# LED.net
KiCad netlist of a schematic drawn in Altium Designer
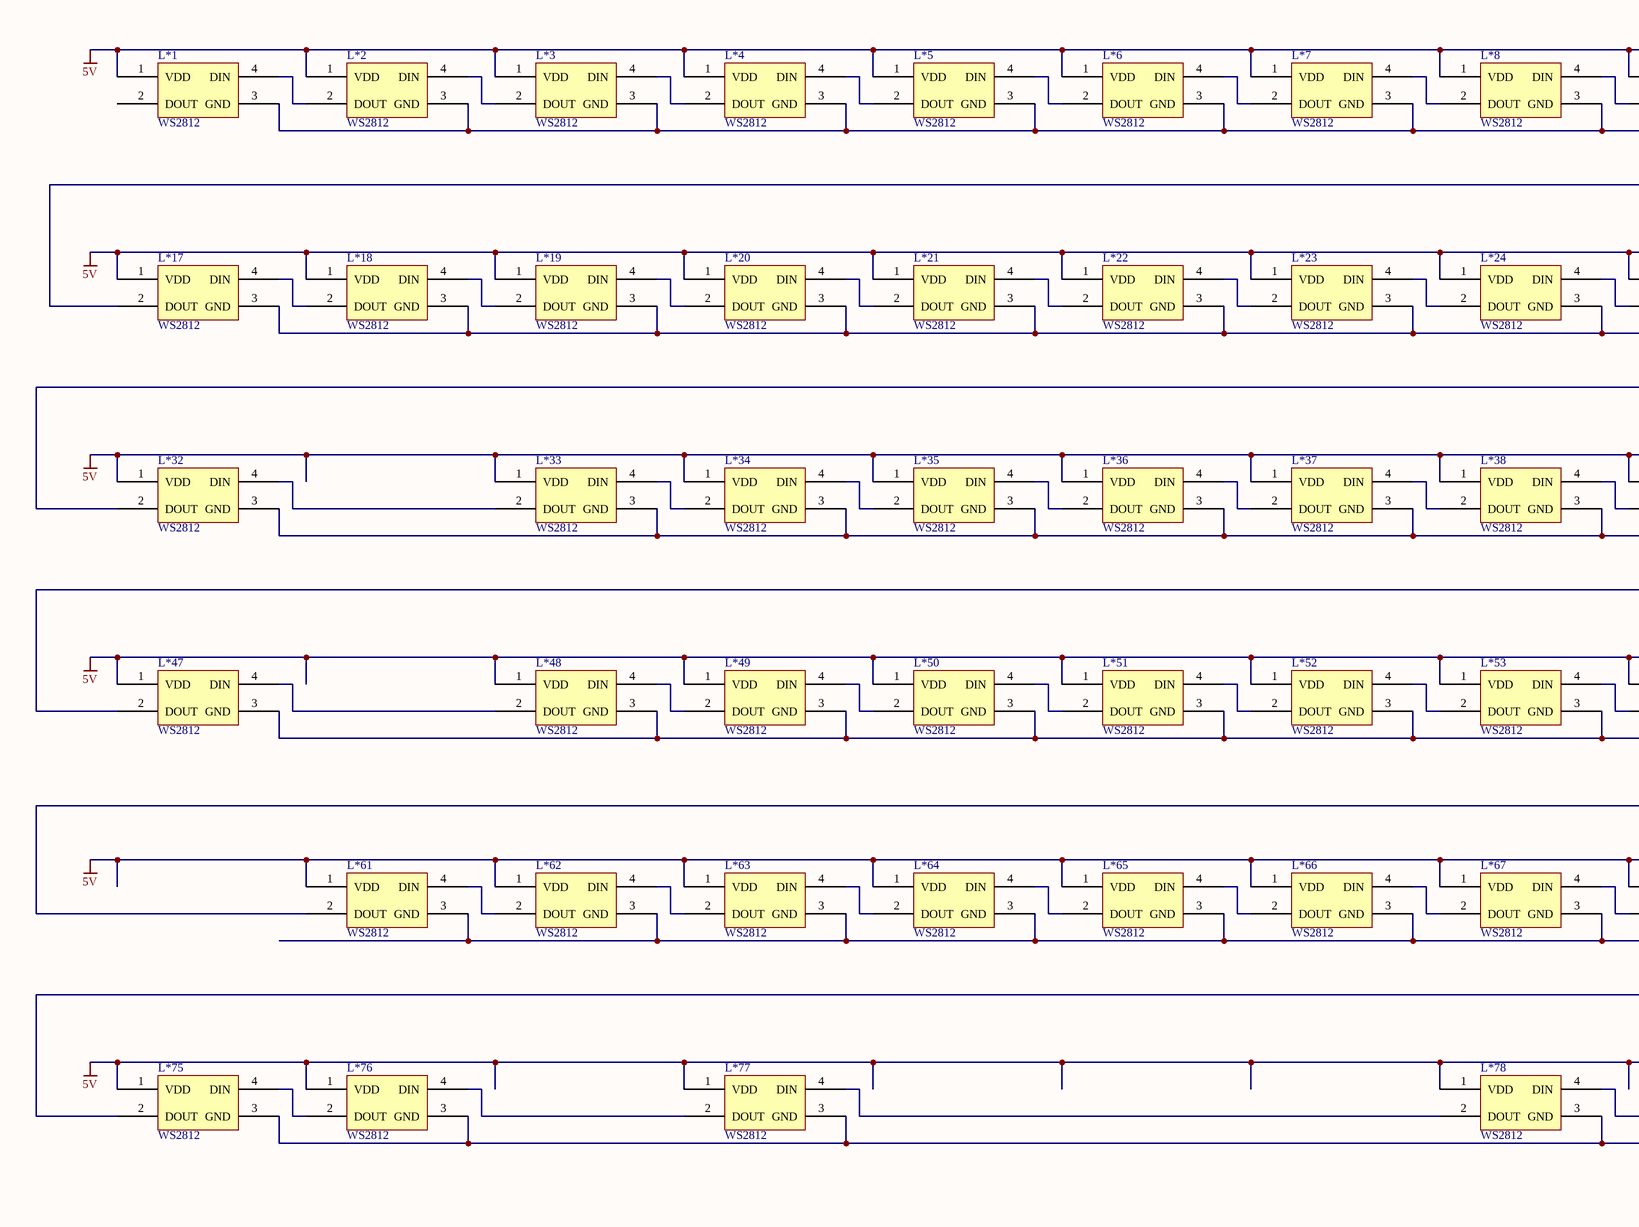
[diagram p0: LED.SchDoc, left]
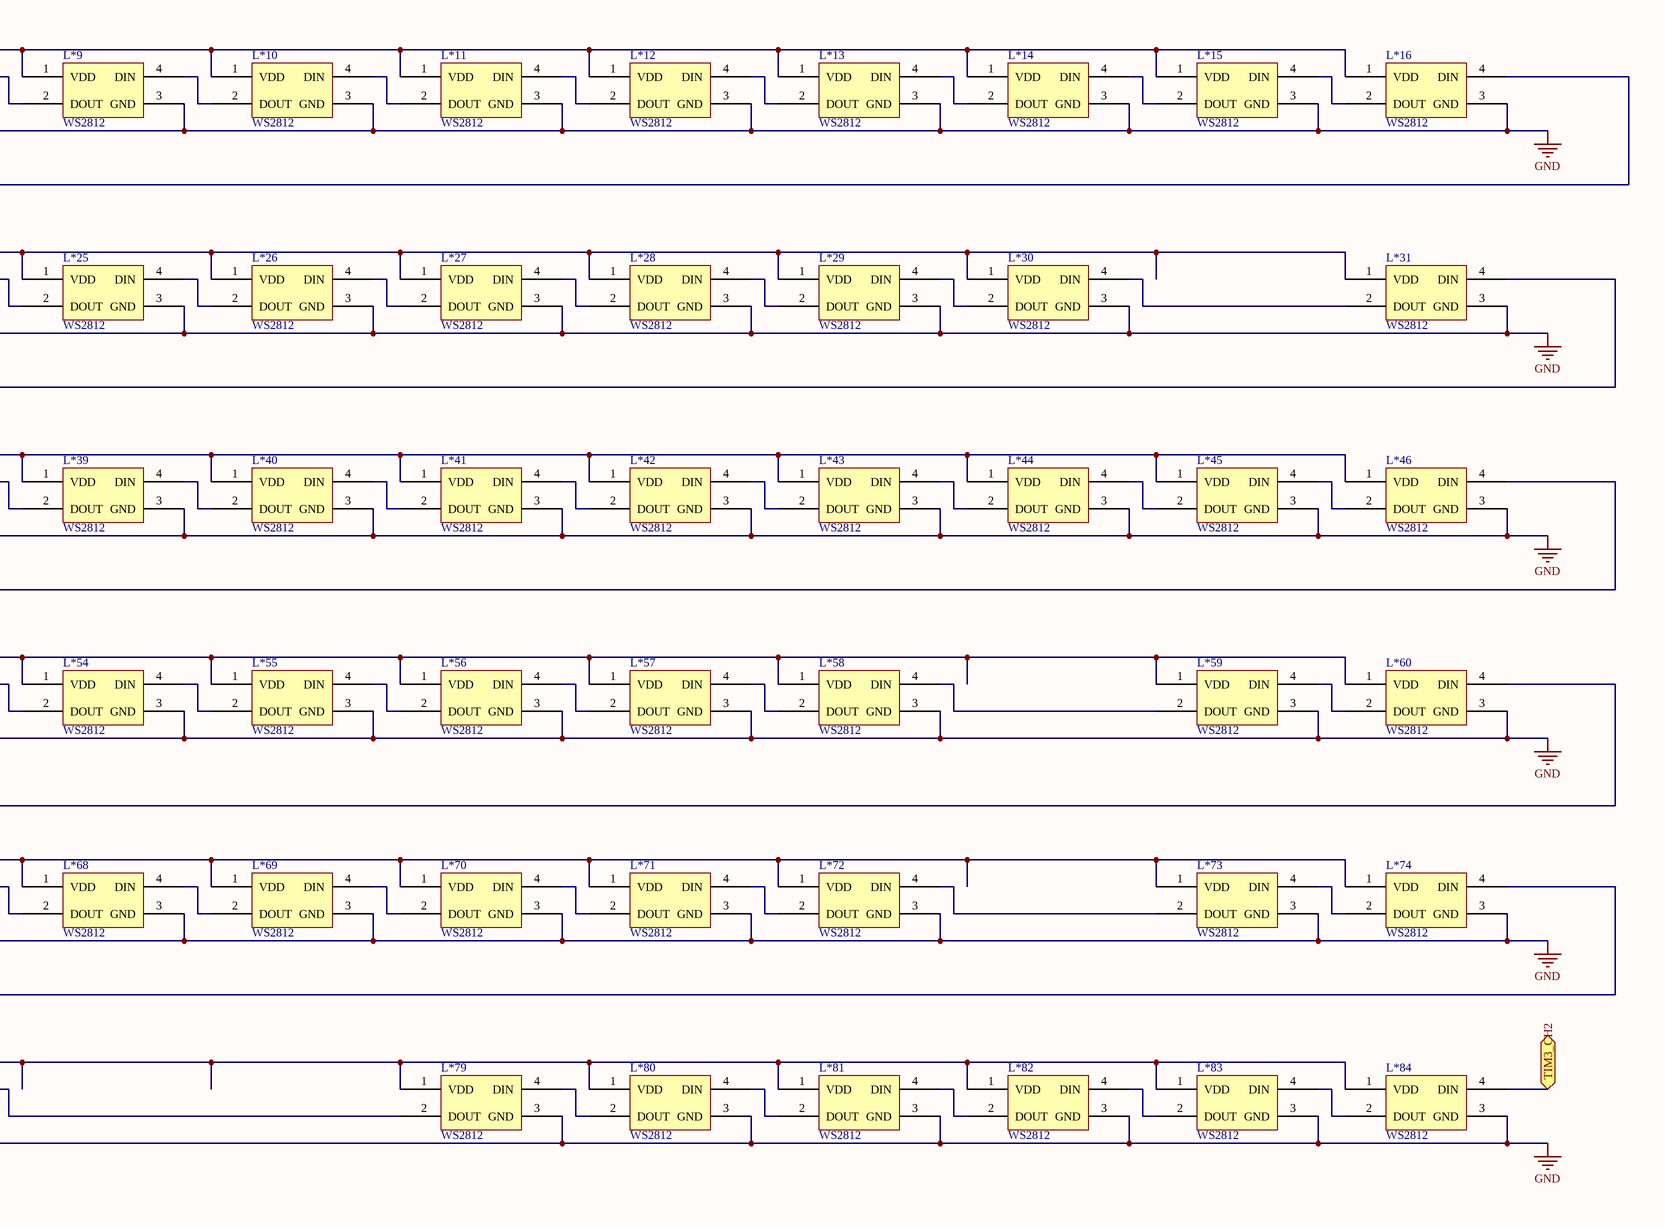
[diagram p1: LED.SchDoc, right]

(export (version "E")
  (design (tool "Eeschema 10.0.6"))
  (components
    (comp (ref "L*1") (value "WS2812") (footprint "3528-4反贴") (libsource (lib "Fancy") (part "WS2812")))
    (comp (ref "L*2") (value "WS2812") (footprint "3528-4反贴") (libsource (lib "Fancy") (part "WS2812")))
    (comp (ref "L*3") (value "WS2812") (footprint "3528-4反贴") (libsource (lib "Fancy") (part "WS2812")))
    (comp (ref "L*4") (value "WS2812") (footprint "3528-4反贴") (libsource (lib "Fancy") (part "WS2812")))
    (comp (ref "L*5") (value "WS2812") (footprint "3528-4反贴") (libsource (lib "Fancy") (part "WS2812")))
    (comp (ref "L*6") (value "WS2812") (footprint "3528-4反贴") (libsource (lib "Fancy") (part "WS2812")))
    (comp (ref "L*7") (value "WS2812") (footprint "3528-4反贴") (libsource (lib "Fancy") (part "WS2812")))
    (comp (ref "L*8") (value "WS2812") (footprint "3528-4反贴") (libsource (lib "Fancy") (part "WS2812")))
    (comp (ref "L*9") (value "WS2812") (footprint "3528-4反贴") (libsource (lib "Fancy") (part "WS2812")))
    (comp (ref "L*10") (value "WS2812") (footprint "3528-4反贴") (libsource (lib "Fancy") (part "WS2812")))
    (comp (ref "L*11") (value "WS2812") (footprint "3528-4反贴") (libsource (lib "Fancy") (part "WS2812")))
    (comp (ref "L*12") (value "WS2812") (footprint "3528-4反贴") (libsource (lib "Fancy") (part "WS2812")))
    (comp (ref "L*13") (value "WS2812") (footprint "3528-4反贴") (libsource (lib "Fancy") (part "WS2812")))
    (comp (ref "L*14") (value "WS2812") (footprint "3528-4反贴") (libsource (lib "Fancy") (part "WS2812")))
    (comp (ref "L*15") (value "WS2812") (footprint "3528-4反贴") (libsource (lib "Fancy") (part "WS2812")))
    (comp (ref "L*16") (value "WS2812") (footprint "3528-4反贴") (libsource (lib "Fancy") (part "WS2812")))
    (comp (ref "L*17") (value "WS2812") (footprint "3528-4反贴") (libsource (lib "Fancy") (part "WS2812")))
    (comp (ref "L*18") (value "WS2812") (footprint "3528-4反贴") (libsource (lib "Fancy") (part "WS2812")))
    (comp (ref "L*19") (value "WS2812") (footprint "3528-4反贴") (libsource (lib "Fancy") (part "WS2812")))
    (comp (ref "L*20") (value "WS2812") (footprint "3528-4反贴") (libsource (lib "Fancy") (part "WS2812")))
    (comp (ref "L*21") (value "WS2812") (footprint "3528-4反贴") (libsource (lib "Fancy") (part "WS2812")))
    (comp (ref "L*22") (value "WS2812") (footprint "3528-4反贴") (libsource (lib "Fancy") (part "WS2812")))
    (comp (ref "L*23") (value "WS2812") (footprint "3528-4反贴") (libsource (lib "Fancy") (part "WS2812")))
    (comp (ref "L*24") (value "WS2812") (footprint "3528-4反贴") (libsource (lib "Fancy") (part "WS2812")))
    (comp (ref "L*25") (value "WS2812") (footprint "3528-4反贴") (libsource (lib "Fancy") (part "WS2812")))
    (comp (ref "L*26") (value "WS2812") (footprint "3528-4反贴") (libsource (lib "Fancy") (part "WS2812")))
    (comp (ref "L*27") (value "WS2812") (footprint "3528-4反贴") (libsource (lib "Fancy") (part "WS2812")))
    (comp (ref "L*28") (value "WS2812") (footprint "3528-4反贴") (libsource (lib "Fancy") (part "WS2812")))
    (comp (ref "L*29") (value "WS2812") (footprint "3528-4反贴") (libsource (lib "Fancy") (part "WS2812")))
    (comp (ref "L*30") (value "WS2812") (footprint "3528-4反贴") (libsource (lib "Fancy") (part "WS2812")))
    (comp (ref "L*31") (value "WS2812") (footprint "3528-4反贴") (libsource (lib "Fancy") (part "WS2812")))
    (comp (ref "L*32") (value "WS2812") (footprint "3528-4反贴") (libsource (lib "Fancy") (part "WS2812")))
    (comp (ref "L*33") (value "WS2812") (footprint "3528-4反贴") (libsource (lib "Fancy") (part "WS2812")))
    (comp (ref "L*34") (value "WS2812") (footprint "3528-4反贴") (libsource (lib "Fancy") (part "WS2812")))
    (comp (ref "L*35") (value "WS2812") (footprint "3528-4反贴") (libsource (lib "Fancy") (part "WS2812")))
    (comp (ref "L*36") (value "WS2812") (footprint "3528-4反贴") (libsource (lib "Fancy") (part "WS2812")))
    (comp (ref "L*37") (value "WS2812") (footprint "3528-4反贴") (libsource (lib "Fancy") (part "WS2812")))
    (comp (ref "L*38") (value "WS2812") (footprint "3528-4反贴") (libsource (lib "Fancy") (part "WS2812")))
    (comp (ref "L*39") (value "WS2812") (footprint "3528-4反贴") (libsource (lib "Fancy") (part "WS2812")))
    (comp (ref "L*40") (value "WS2812") (footprint "3528-4反贴") (libsource (lib "Fancy") (part "WS2812")))
    (comp (ref "L*41") (value "WS2812") (footprint "3528-4反贴") (libsource (lib "Fancy") (part "WS2812")))
    (comp (ref "L*42") (value "WS2812") (footprint "3528-4反贴") (libsource (lib "Fancy") (part "WS2812")))
    (comp (ref "L*43") (value "WS2812") (footprint "3528-4反贴") (libsource (lib "Fancy") (part "WS2812")))
    (comp (ref "L*44") (value "WS2812") (footprint "3528-4反贴") (libsource (lib "Fancy") (part "WS2812")))
    (comp (ref "L*45") (value "WS2812") (footprint "3528-4反贴") (libsource (lib "Fancy") (part "WS2812")))
    (comp (ref "L*46") (value "WS2812") (footprint "3528-4反贴") (libsource (lib "Fancy") (part "WS2812")))
    (comp (ref "L*47") (value "WS2812") (footprint "3528-4反贴") (libsource (lib "Fancy") (part "WS2812")))
    (comp (ref "L*48") (value "WS2812") (footprint "3528-4反贴") (libsource (lib "Fancy") (part "WS2812")))
    (comp (ref "L*49") (value "WS2812") (footprint "3528-4反贴") (libsource (lib "Fancy") (part "WS2812")))
    (comp (ref "L*50") (value "WS2812") (footprint "3528-4反贴") (libsource (lib "Fancy") (part "WS2812")))
    (comp (ref "L*51") (value "WS2812") (footprint "3528-4反贴") (libsource (lib "Fancy") (part "WS2812")))
    (comp (ref "L*52") (value "WS2812") (footprint "3528-4反贴") (libsource (lib "Fancy") (part "WS2812")))
    (comp (ref "L*53") (value "WS2812") (footprint "3528-4反贴") (libsource (lib "Fancy") (part "WS2812")))
    (comp (ref "L*54") (value "WS2812") (footprint "3528-4反贴") (libsource (lib "Fancy") (part "WS2812")))
    (comp (ref "L*55") (value "WS2812") (footprint "3528-4反贴") (libsource (lib "Fancy") (part "WS2812")))
    (comp (ref "L*56") (value "WS2812") (footprint "3528-4反贴") (libsource (lib "Fancy") (part "WS2812")))
    (comp (ref "L*57") (value "WS2812") (footprint "3528-4反贴") (libsource (lib "Fancy") (part "WS2812")))
    (comp (ref "L*58") (value "WS2812") (footprint "3528-4反贴") (libsource (lib "Fancy") (part "WS2812")))
    (comp (ref "L*59") (value "WS2812") (footprint "3528-4反贴") (libsource (lib "Fancy") (part "WS2812")))
    (comp (ref "L*60") (value "WS2812") (footprint "3528-4反贴") (libsource (lib "Fancy") (part "WS2812")))
    (comp (ref "L*61") (value "WS2812") (footprint "3528-4反贴") (libsource (lib "Fancy") (part "WS2812")))
    (comp (ref "L*62") (value "WS2812") (footprint "3528-4反贴") (libsource (lib "Fancy") (part "WS2812")))
    (comp (ref "L*63") (value "WS2812") (footprint "3528-4反贴") (libsource (lib "Fancy") (part "WS2812")))
    (comp (ref "L*64") (value "WS2812") (footprint "3528-4反贴") (libsource (lib "Fancy") (part "WS2812")))
    (comp (ref "L*65") (value "WS2812") (footprint "3528-4反贴") (libsource (lib "Fancy") (part "WS2812")))
    (comp (ref "L*66") (value "WS2812") (footprint "3528-4反贴") (libsource (lib "Fancy") (part "WS2812")))
    (comp (ref "L*67") (value "WS2812") (footprint "3528-4反贴") (libsource (lib "Fancy") (part "WS2812")))
    (comp (ref "L*68") (value "WS2812") (footprint "3528-4反贴") (libsource (lib "Fancy") (part "WS2812")))
    (comp (ref "L*69") (value "WS2812") (footprint "3528-4反贴") (libsource (lib "Fancy") (part "WS2812")))
    (comp (ref "L*70") (value "WS2812") (footprint "3528-4反贴") (libsource (lib "Fancy") (part "WS2812")))
    (comp (ref "L*71") (value "WS2812") (footprint "3528-4反贴") (libsource (lib "Fancy") (part "WS2812")))
    (comp (ref "L*72") (value "WS2812") (footprint "3528-4反贴") (libsource (lib "Fancy") (part "WS2812")))
    (comp (ref "L*73") (value "WS2812") (footprint "3528-4反贴") (libsource (lib "Fancy") (part "WS2812")))
    (comp (ref "L*74") (value "WS2812") (footprint "3528-4反贴") (libsource (lib "Fancy") (part "WS2812")))
    (comp (ref "L*75") (value "WS2812") (footprint "3528-4反贴") (libsource (lib "Fancy") (part "WS2812")))
    (comp (ref "L*76") (value "WS2812") (footprint "3528-4反贴") (libsource (lib "Fancy") (part "WS2812")))
    (comp (ref "L*77") (value "WS2812") (footprint "3528-4反贴") (libsource (lib "Fancy") (part "WS2812")))
    (comp (ref "L*78") (value "WS2812") (footprint "3528-4反贴") (libsource (lib "Fancy") (part "WS2812")))
    (comp (ref "L*79") (value "WS2812") (footprint "3528-4反贴") (libsource (lib "Fancy") (part "WS2812")))
    (comp (ref "L*80") (value "WS2812") (footprint "3528-4反贴") (libsource (lib "Fancy") (part "WS2812")))
    (comp (ref "L*81") (value "WS2812") (footprint "3528-4反贴") (libsource (lib "Fancy") (part "WS2812")))
    (comp (ref "L*82") (value "WS2812") (footprint "3528-4反贴") (libsource (lib "Fancy") (part "WS2812")))
    (comp (ref "L*83") (value "WS2812") (footprint "3528-4反贴") (libsource (lib "Fancy") (part "WS2812")))
    (comp (ref "L*84") (value "WS2812") (footprint "3528-4反贴") (libsource (lib "Fancy") (part "WS2812")))
  )
  (nets
    (net (code "1") (name "/TIM3_CH2") (class "Default")
      (node (ref "L*84") (pin "4") (pinfunction "DIN_4") (pintype "passive"))
    )
    (net (code "2") (name "5V") (class "Default")
      (node (ref "L*1") (pin "1") (pinfunction "VDD_1") (pintype "passive"))
      (node (ref "L*10") (pin "1") (pinfunction "VDD_1") (pintype "passive"))
      (node (ref "L*11") (pin "1") (pinfunction "VDD_1") (pintype "passive"))
      (node (ref "L*12") (pin "1") (pinfunction "VDD_1") (pintype "passive"))
      (node (ref "L*13") (pin "1") (pinfunction "VDD_1") (pintype "passive"))
      (node (ref "L*14") (pin "1") (pinfunction "VDD_1") (pintype "passive"))
      (node (ref "L*15") (pin "1") (pinfunction "VDD_1") (pintype "passive"))
      (node (ref "L*16") (pin "1") (pinfunction "VDD_1") (pintype "passive"))
      (node (ref "L*17") (pin "1") (pinfunction "VDD_1") (pintype "passive"))
      (node (ref "L*18") (pin "1") (pinfunction "VDD_1") (pintype "passive"))
      (node (ref "L*19") (pin "1") (pinfunction "VDD_1") (pintype "passive"))
      (node (ref "L*2") (pin "1") (pinfunction "VDD_1") (pintype "passive"))
      (node (ref "L*20") (pin "1") (pinfunction "VDD_1") (pintype "passive"))
      (node (ref "L*21") (pin "1") (pinfunction "VDD_1") (pintype "passive"))
      (node (ref "L*22") (pin "1") (pinfunction "VDD_1") (pintype "passive"))
      (node (ref "L*23") (pin "1") (pinfunction "VDD_1") (pintype "passive"))
      (node (ref "L*24") (pin "1") (pinfunction "VDD_1") (pintype "passive"))
      (node (ref "L*25") (pin "1") (pinfunction "VDD_1") (pintype "passive"))
      (node (ref "L*26") (pin "1") (pinfunction "VDD_1") (pintype "passive"))
      (node (ref "L*27") (pin "1") (pinfunction "VDD_1") (pintype "passive"))
      (node (ref "L*28") (pin "1") (pinfunction "VDD_1") (pintype "passive"))
      (node (ref "L*29") (pin "1") (pinfunction "VDD_1") (pintype "passive"))
      (node (ref "L*3") (pin "1") (pinfunction "VDD_1") (pintype "passive"))
      (node (ref "L*30") (pin "1") (pinfunction "VDD_1") (pintype "passive"))
      (node (ref "L*31") (pin "1") (pinfunction "VDD_1") (pintype "passive"))
      (node (ref "L*32") (pin "1") (pinfunction "VDD_1") (pintype "passive"))
      (node (ref "L*33") (pin "1") (pinfunction "VDD_1") (pintype "passive"))
      (node (ref "L*34") (pin "1") (pinfunction "VDD_1") (pintype "passive"))
      (node (ref "L*35") (pin "1") (pinfunction "VDD_1") (pintype "passive"))
      (node (ref "L*36") (pin "1") (pinfunction "VDD_1") (pintype "passive"))
      (node (ref "L*37") (pin "1") (pinfunction "VDD_1") (pintype "passive"))
      (node (ref "L*38") (pin "1") (pinfunction "VDD_1") (pintype "passive"))
      (node (ref "L*39") (pin "1") (pinfunction "VDD_1") (pintype "passive"))
      (node (ref "L*4") (pin "1") (pinfunction "VDD_1") (pintype "passive"))
      (node (ref "L*40") (pin "1") (pinfunction "VDD_1") (pintype "passive"))
      (node (ref "L*41") (pin "1") (pinfunction "VDD_1") (pintype "passive"))
      (node (ref "L*42") (pin "1") (pinfunction "VDD_1") (pintype "passive"))
      (node (ref "L*43") (pin "1") (pinfunction "VDD_1") (pintype "passive"))
      (node (ref "L*44") (pin "1") (pinfunction "VDD_1") (pintype "passive"))
      (node (ref "L*45") (pin "1") (pinfunction "VDD_1") (pintype "passive"))
      (node (ref "L*46") (pin "1") (pinfunction "VDD_1") (pintype "passive"))
      (node (ref "L*47") (pin "1") (pinfunction "VDD_1") (pintype "passive"))
      (node (ref "L*48") (pin "1") (pinfunction "VDD_1") (pintype "passive"))
      (node (ref "L*49") (pin "1") (pinfunction "VDD_1") (pintype "passive"))
      (node (ref "L*5") (pin "1") (pinfunction "VDD_1") (pintype "passive"))
      (node (ref "L*50") (pin "1") (pinfunction "VDD_1") (pintype "passive"))
      (node (ref "L*51") (pin "1") (pinfunction "VDD_1") (pintype "passive"))
      (node (ref "L*52") (pin "1") (pinfunction "VDD_1") (pintype "passive"))
      (node (ref "L*53") (pin "1") (pinfunction "VDD_1") (pintype "passive"))
      (node (ref "L*54") (pin "1") (pinfunction "VDD_1") (pintype "passive"))
      (node (ref "L*55") (pin "1") (pinfunction "VDD_1") (pintype "passive"))
      (node (ref "L*56") (pin "1") (pinfunction "VDD_1") (pintype "passive"))
      (node (ref "L*57") (pin "1") (pinfunction "VDD_1") (pintype "passive"))
      (node (ref "L*58") (pin "1") (pinfunction "VDD_1") (pintype "passive"))
      (node (ref "L*59") (pin "1") (pinfunction "VDD_1") (pintype "passive"))
      (node (ref "L*6") (pin "1") (pinfunction "VDD_1") (pintype "passive"))
      (node (ref "L*60") (pin "1") (pinfunction "VDD_1") (pintype "passive"))
      (node (ref "L*61") (pin "1") (pinfunction "VDD_1") (pintype "passive"))
      (node (ref "L*62") (pin "1") (pinfunction "VDD_1") (pintype "passive"))
      (node (ref "L*63") (pin "1") (pinfunction "VDD_1") (pintype "passive"))
      (node (ref "L*64") (pin "1") (pinfunction "VDD_1") (pintype "passive"))
      (node (ref "L*65") (pin "1") (pinfunction "VDD_1") (pintype "passive"))
      (node (ref "L*66") (pin "1") (pinfunction "VDD_1") (pintype "passive"))
      (node (ref "L*67") (pin "1") (pinfunction "VDD_1") (pintype "passive"))
      (node (ref "L*68") (pin "1") (pinfunction "VDD_1") (pintype "passive"))
      (node (ref "L*69") (pin "1") (pinfunction "VDD_1") (pintype "passive"))
      (node (ref "L*7") (pin "1") (pinfunction "VDD_1") (pintype "passive"))
      (node (ref "L*70") (pin "1") (pinfunction "VDD_1") (pintype "passive"))
      (node (ref "L*71") (pin "1") (pinfunction "VDD_1") (pintype "passive"))
      (node (ref "L*72") (pin "1") (pinfunction "VDD_1") (pintype "passive"))
      (node (ref "L*73") (pin "1") (pinfunction "VDD_1") (pintype "passive"))
      (node (ref "L*74") (pin "1") (pinfunction "VDD_1") (pintype "passive"))
      (node (ref "L*75") (pin "1") (pinfunction "VDD_1") (pintype "passive"))
      (node (ref "L*76") (pin "1") (pinfunction "VDD_1") (pintype "passive"))
      (node (ref "L*77") (pin "1") (pinfunction "VDD_1") (pintype "passive"))
      (node (ref "L*78") (pin "1") (pinfunction "VDD_1") (pintype "passive"))
      (node (ref "L*79") (pin "1") (pinfunction "VDD_1") (pintype "passive"))
      (node (ref "L*8") (pin "1") (pinfunction "VDD_1") (pintype "passive"))
      (node (ref "L*80") (pin "1") (pinfunction "VDD_1") (pintype "passive"))
      (node (ref "L*81") (pin "1") (pinfunction "VDD_1") (pintype "passive"))
      (node (ref "L*82") (pin "1") (pinfunction "VDD_1") (pintype "passive"))
      (node (ref "L*83") (pin "1") (pinfunction "VDD_1") (pintype "passive"))
      (node (ref "L*84") (pin "1") (pinfunction "VDD_1") (pintype "passive"))
      (node (ref "L*9") (pin "1") (pinfunction "VDD_1") (pintype "passive"))
    )
    (net (code "3") (name "GND") (class "Default")
      (node (ref "L*1") (pin "3") (pinfunction "GND_3") (pintype "passive"))
      (node (ref "L*10") (pin "3") (pinfunction "GND_3") (pintype "passive"))
      (node (ref "L*11") (pin "3") (pinfunction "GND_3") (pintype "passive"))
      (node (ref "L*12") (pin "3") (pinfunction "GND_3") (pintype "passive"))
      (node (ref "L*13") (pin "3") (pinfunction "GND_3") (pintype "passive"))
      (node (ref "L*14") (pin "3") (pinfunction "GND_3") (pintype "passive"))
      (node (ref "L*15") (pin "3") (pinfunction "GND_3") (pintype "passive"))
      (node (ref "L*16") (pin "3") (pinfunction "GND_3") (pintype "passive"))
      (node (ref "L*17") (pin "3") (pinfunction "GND_3") (pintype "passive"))
      (node (ref "L*18") (pin "3") (pinfunction "GND_3") (pintype "passive"))
      (node (ref "L*19") (pin "3") (pinfunction "GND_3") (pintype "passive"))
      (node (ref "L*2") (pin "3") (pinfunction "GND_3") (pintype "passive"))
      (node (ref "L*20") (pin "3") (pinfunction "GND_3") (pintype "passive"))
      (node (ref "L*21") (pin "3") (pinfunction "GND_3") (pintype "passive"))
      (node (ref "L*22") (pin "3") (pinfunction "GND_3") (pintype "passive"))
      (node (ref "L*23") (pin "3") (pinfunction "GND_3") (pintype "passive"))
      (node (ref "L*24") (pin "3") (pinfunction "GND_3") (pintype "passive"))
      (node (ref "L*25") (pin "3") (pinfunction "GND_3") (pintype "passive"))
      (node (ref "L*26") (pin "3") (pinfunction "GND_3") (pintype "passive"))
      (node (ref "L*27") (pin "3") (pinfunction "GND_3") (pintype "passive"))
      (node (ref "L*28") (pin "3") (pinfunction "GND_3") (pintype "passive"))
      (node (ref "L*29") (pin "3") (pinfunction "GND_3") (pintype "passive"))
      (node (ref "L*3") (pin "3") (pinfunction "GND_3") (pintype "passive"))
      (node (ref "L*30") (pin "3") (pinfunction "GND_3") (pintype "passive"))
      (node (ref "L*31") (pin "3") (pinfunction "GND_3") (pintype "passive"))
      (node (ref "L*32") (pin "3") (pinfunction "GND_3") (pintype "passive"))
      (node (ref "L*33") (pin "3") (pinfunction "GND_3") (pintype "passive"))
      (node (ref "L*34") (pin "3") (pinfunction "GND_3") (pintype "passive"))
      (node (ref "L*35") (pin "3") (pinfunction "GND_3") (pintype "passive"))
      (node (ref "L*36") (pin "3") (pinfunction "GND_3") (pintype "passive"))
      (node (ref "L*37") (pin "3") (pinfunction "GND_3") (pintype "passive"))
      (node (ref "L*38") (pin "3") (pinfunction "GND_3") (pintype "passive"))
      (node (ref "L*39") (pin "3") (pinfunction "GND_3") (pintype "passive"))
      (node (ref "L*4") (pin "3") (pinfunction "GND_3") (pintype "passive"))
      (node (ref "L*40") (pin "3") (pinfunction "GND_3") (pintype "passive"))
      (node (ref "L*41") (pin "3") (pinfunction "GND_3") (pintype "passive"))
      (node (ref "L*42") (pin "3") (pinfunction "GND_3") (pintype "passive"))
      (node (ref "L*43") (pin "3") (pinfunction "GND_3") (pintype "passive"))
      (node (ref "L*44") (pin "3") (pinfunction "GND_3") (pintype "passive"))
      (node (ref "L*45") (pin "3") (pinfunction "GND_3") (pintype "passive"))
      (node (ref "L*46") (pin "3") (pinfunction "GND_3") (pintype "passive"))
      (node (ref "L*47") (pin "3") (pinfunction "GND_3") (pintype "passive"))
      (node (ref "L*48") (pin "3") (pinfunction "GND_3") (pintype "passive"))
      (node (ref "L*49") (pin "3") (pinfunction "GND_3") (pintype "passive"))
      (node (ref "L*5") (pin "3") (pinfunction "GND_3") (pintype "passive"))
      (node (ref "L*50") (pin "3") (pinfunction "GND_3") (pintype "passive"))
      (node (ref "L*51") (pin "3") (pinfunction "GND_3") (pintype "passive"))
      (node (ref "L*52") (pin "3") (pinfunction "GND_3") (pintype "passive"))
      (node (ref "L*53") (pin "3") (pinfunction "GND_3") (pintype "passive"))
      (node (ref "L*54") (pin "3") (pinfunction "GND_3") (pintype "passive"))
      (node (ref "L*55") (pin "3") (pinfunction "GND_3") (pintype "passive"))
      (node (ref "L*56") (pin "3") (pinfunction "GND_3") (pintype "passive"))
      (node (ref "L*57") (pin "3") (pinfunction "GND_3") (pintype "passive"))
      (node (ref "L*58") (pin "3") (pinfunction "GND_3") (pintype "passive"))
      (node (ref "L*59") (pin "3") (pinfunction "GND_3") (pintype "passive"))
      (node (ref "L*6") (pin "3") (pinfunction "GND_3") (pintype "passive"))
      (node (ref "L*60") (pin "3") (pinfunction "GND_3") (pintype "passive"))
      (node (ref "L*61") (pin "3") (pinfunction "GND_3") (pintype "passive"))
      (node (ref "L*62") (pin "3") (pinfunction "GND_3") (pintype "passive"))
      (node (ref "L*63") (pin "3") (pinfunction "GND_3") (pintype "passive"))
      (node (ref "L*64") (pin "3") (pinfunction "GND_3") (pintype "passive"))
      (node (ref "L*65") (pin "3") (pinfunction "GND_3") (pintype "passive"))
      (node (ref "L*66") (pin "3") (pinfunction "GND_3") (pintype "passive"))
      (node (ref "L*67") (pin "3") (pinfunction "GND_3") (pintype "passive"))
      (node (ref "L*68") (pin "3") (pinfunction "GND_3") (pintype "passive"))
      (node (ref "L*69") (pin "3") (pinfunction "GND_3") (pintype "passive"))
      (node (ref "L*7") (pin "3") (pinfunction "GND_3") (pintype "passive"))
      (node (ref "L*70") (pin "3") (pinfunction "GND_3") (pintype "passive"))
      (node (ref "L*71") (pin "3") (pinfunction "GND_3") (pintype "passive"))
      (node (ref "L*72") (pin "3") (pinfunction "GND_3") (pintype "passive"))
      (node (ref "L*73") (pin "3") (pinfunction "GND_3") (pintype "passive"))
      (node (ref "L*74") (pin "3") (pinfunction "GND_3") (pintype "passive"))
      (node (ref "L*75") (pin "3") (pinfunction "GND_3") (pintype "passive"))
      (node (ref "L*76") (pin "3") (pinfunction "GND_3") (pintype "passive"))
      (node (ref "L*77") (pin "3") (pinfunction "GND_3") (pintype "passive"))
      (node (ref "L*78") (pin "3") (pinfunction "GND_3") (pintype "passive"))
      (node (ref "L*79") (pin "3") (pinfunction "GND_3") (pintype "passive"))
      (node (ref "L*8") (pin "3") (pinfunction "GND_3") (pintype "passive"))
      (node (ref "L*80") (pin "3") (pinfunction "GND_3") (pintype "passive"))
      (node (ref "L*81") (pin "3") (pinfunction "GND_3") (pintype "passive"))
      (node (ref "L*82") (pin "3") (pinfunction "GND_3") (pintype "passive"))
      (node (ref "L*83") (pin "3") (pinfunction "GND_3") (pintype "passive"))
      (node (ref "L*84") (pin "3") (pinfunction "GND_3") (pintype "passive"))
      (node (ref "L*9") (pin "3") (pinfunction "GND_3") (pintype "passive"))
    )
    (net (code "4") (name "Net-(L*1-DIN)") (class "Default")
      (node (ref "L*1") (pin "4") (pinfunction "DIN_4") (pintype "passive"))
      (node (ref "L*2") (pin "2") (pinfunction "DOUT_2") (pintype "passive"))
    )
    (net (code "5") (name "Net-(L*2-DIN)") (class "Default")
      (node (ref "L*2") (pin "4") (pinfunction "DIN_4") (pintype "passive"))
      (node (ref "L*3") (pin "2") (pinfunction "DOUT_2") (pintype "passive"))
    )
    (net (code "6") (name "Net-(L*3-DIN)") (class "Default")
      (node (ref "L*3") (pin "4") (pinfunction "DIN_4") (pintype "passive"))
      (node (ref "L*4") (pin "2") (pinfunction "DOUT_2") (pintype "passive"))
    )
    (net (code "7") (name "Net-(L*4-DIN)") (class "Default")
      (node (ref "L*4") (pin "4") (pinfunction "DIN_4") (pintype "passive"))
      (node (ref "L*5") (pin "2") (pinfunction "DOUT_2") (pintype "passive"))
    )
    (net (code "8") (name "Net-(L*5-DIN)") (class "Default")
      (node (ref "L*5") (pin "4") (pinfunction "DIN_4") (pintype "passive"))
      (node (ref "L*6") (pin "2") (pinfunction "DOUT_2") (pintype "passive"))
    )
    (net (code "9") (name "Net-(L*6-DIN)") (class "Default")
      (node (ref "L*6") (pin "4") (pinfunction "DIN_4") (pintype "passive"))
      (node (ref "L*7") (pin "2") (pinfunction "DOUT_2") (pintype "passive"))
    )
    (net (code "10") (name "Net-(L*7-DIN)") (class "Default")
      (node (ref "L*7") (pin "4") (pinfunction "DIN_4") (pintype "passive"))
      (node (ref "L*8") (pin "2") (pinfunction "DOUT_2") (pintype "passive"))
    )
    (net (code "11") (name "Net-(L*8-DIN)") (class "Default")
      (node (ref "L*8") (pin "4") (pinfunction "DIN_4") (pintype "passive"))
      (node (ref "L*9") (pin "2") (pinfunction "DOUT_2") (pintype "passive"))
    )
    (net (code "12") (name "Net-(L*10-DIN)") (class "Default")
      (node (ref "L*10") (pin "4") (pinfunction "DIN_4") (pintype "passive"))
      (node (ref "L*11") (pin "2") (pinfunction "DOUT_2") (pintype "passive"))
    )
    (net (code "13") (name "Net-(L*10-DOUT)") (class "Default")
      (node (ref "L*10") (pin "2") (pinfunction "DOUT_2") (pintype "passive"))
      (node (ref "L*9") (pin "4") (pinfunction "DIN_4") (pintype "passive"))
    )
    (net (code "14") (name "Net-(L*11-DIN)") (class "Default")
      (node (ref "L*11") (pin "4") (pinfunction "DIN_4") (pintype "passive"))
      (node (ref "L*12") (pin "2") (pinfunction "DOUT_2") (pintype "passive"))
    )
    (net (code "15") (name "Net-(L*12-DIN)") (class "Default")
      (node (ref "L*12") (pin "4") (pinfunction "DIN_4") (pintype "passive"))
      (node (ref "L*13") (pin "2") (pinfunction "DOUT_2") (pintype "passive"))
    )
    (net (code "16") (name "Net-(L*13-DIN)") (class "Default")
      (node (ref "L*13") (pin "4") (pinfunction "DIN_4") (pintype "passive"))
      (node (ref "L*14") (pin "2") (pinfunction "DOUT_2") (pintype "passive"))
    )
    (net (code "17") (name "Net-(L*14-DIN)") (class "Default")
      (node (ref "L*14") (pin "4") (pinfunction "DIN_4") (pintype "passive"))
      (node (ref "L*15") (pin "2") (pinfunction "DOUT_2") (pintype "passive"))
    )
    (net (code "18") (name "Net-(L*15-DIN)") (class "Default")
      (node (ref "L*15") (pin "4") (pinfunction "DIN_4") (pintype "passive"))
      (node (ref "L*16") (pin "2") (pinfunction "DOUT_2") (pintype "passive"))
    )
    (net (code "19") (name "Net-(L*16-DIN)") (class "Default")
      (node (ref "L*16") (pin "4") (pinfunction "DIN_4") (pintype "passive"))
      (node (ref "L*17") (pin "2") (pinfunction "DOUT_2") (pintype "passive"))
    )
    (net (code "20") (name "Net-(L*17-DIN)") (class "Default")
      (node (ref "L*17") (pin "4") (pinfunction "DIN_4") (pintype "passive"))
      (node (ref "L*18") (pin "2") (pinfunction "DOUT_2") (pintype "passive"))
    )
    (net (code "21") (name "Net-(L*18-DIN)") (class "Default")
      (node (ref "L*18") (pin "4") (pinfunction "DIN_4") (pintype "passive"))
      (node (ref "L*19") (pin "2") (pinfunction "DOUT_2") (pintype "passive"))
    )
    (net (code "22") (name "Net-(L*19-DIN)") (class "Default")
      (node (ref "L*19") (pin "4") (pinfunction "DIN_4") (pintype "passive"))
      (node (ref "L*20") (pin "2") (pinfunction "DOUT_2") (pintype "passive"))
    )
    (net (code "23") (name "Net-(L*20-DIN)") (class "Default")
      (node (ref "L*20") (pin "4") (pinfunction "DIN_4") (pintype "passive"))
      (node (ref "L*21") (pin "2") (pinfunction "DOUT_2") (pintype "passive"))
    )
    (net (code "24") (name "Net-(L*21-DIN)") (class "Default")
      (node (ref "L*21") (pin "4") (pinfunction "DIN_4") (pintype "passive"))
      (node (ref "L*22") (pin "2") (pinfunction "DOUT_2") (pintype "passive"))
    )
    (net (code "25") (name "Net-(L*22-DIN)") (class "Default")
      (node (ref "L*22") (pin "4") (pinfunction "DIN_4") (pintype "passive"))
      (node (ref "L*23") (pin "2") (pinfunction "DOUT_2") (pintype "passive"))
    )
    (net (code "26") (name "Net-(L*23-DIN)") (class "Default")
      (node (ref "L*23") (pin "4") (pinfunction "DIN_4") (pintype "passive"))
      (node (ref "L*24") (pin "2") (pinfunction "DOUT_2") (pintype "passive"))
    )
    (net (code "27") (name "Net-(L*24-DIN)") (class "Default")
      (node (ref "L*24") (pin "4") (pinfunction "DIN_4") (pintype "passive"))
      (node (ref "L*25") (pin "2") (pinfunction "DOUT_2") (pintype "passive"))
    )
    (net (code "28") (name "Net-(L*25-DIN)") (class "Default")
      (node (ref "L*25") (pin "4") (pinfunction "DIN_4") (pintype "passive"))
      (node (ref "L*26") (pin "2") (pinfunction "DOUT_2") (pintype "passive"))
    )
    (net (code "29") (name "Net-(L*26-DIN)") (class "Default")
      (node (ref "L*26") (pin "4") (pinfunction "DIN_4") (pintype "passive"))
      (node (ref "L*27") (pin "2") (pinfunction "DOUT_2") (pintype "passive"))
    )
    (net (code "30") (name "Net-(L*27-DIN)") (class "Default")
      (node (ref "L*27") (pin "4") (pinfunction "DIN_4") (pintype "passive"))
      (node (ref "L*28") (pin "2") (pinfunction "DOUT_2") (pintype "passive"))
    )
    (net (code "31") (name "Net-(L*28-DIN)") (class "Default")
      (node (ref "L*28") (pin "4") (pinfunction "DIN_4") (pintype "passive"))
      (node (ref "L*29") (pin "2") (pinfunction "DOUT_2") (pintype "passive"))
    )
    (net (code "32") (name "Net-(L*29-DIN)") (class "Default")
      (node (ref "L*29") (pin "4") (pinfunction "DIN_4") (pintype "passive"))
      (node (ref "L*30") (pin "2") (pinfunction "DOUT_2") (pintype "passive"))
    )
    (net (code "33") (name "Net-(L*30-DIN)") (class "Default")
      (node (ref "L*30") (pin "4") (pinfunction "DIN_4") (pintype "passive"))
      (node (ref "L*31") (pin "2") (pinfunction "DOUT_2") (pintype "passive"))
    )
    (net (code "34") (name "Net-(L*31-DIN)") (class "Default")
      (node (ref "L*31") (pin "4") (pinfunction "DIN_4") (pintype "passive"))
      (node (ref "L*32") (pin "2") (pinfunction "DOUT_2") (pintype "passive"))
    )
    (net (code "35") (name "Net-(L*32-DIN)") (class "Default")
      (node (ref "L*32") (pin "4") (pinfunction "DIN_4") (pintype "passive"))
      (node (ref "L*33") (pin "2") (pinfunction "DOUT_2") (pintype "passive"))
    )
    (net (code "36") (name "Net-(L*33-DIN)") (class "Default")
      (node (ref "L*33") (pin "4") (pinfunction "DIN_4") (pintype "passive"))
      (node (ref "L*34") (pin "2") (pinfunction "DOUT_2") (pintype "passive"))
    )
    (net (code "37") (name "Net-(L*34-DIN)") (class "Default")
      (node (ref "L*34") (pin "4") (pinfunction "DIN_4") (pintype "passive"))
      (node (ref "L*35") (pin "2") (pinfunction "DOUT_2") (pintype "passive"))
    )
    (net (code "38") (name "Net-(L*35-DIN)") (class "Default")
      (node (ref "L*35") (pin "4") (pinfunction "DIN_4") (pintype "passive"))
      (node (ref "L*36") (pin "2") (pinfunction "DOUT_2") (pintype "passive"))
    )
    (net (code "39") (name "Net-(L*36-DIN)") (class "Default")
      (node (ref "L*36") (pin "4") (pinfunction "DIN_4") (pintype "passive"))
      (node (ref "L*37") (pin "2") (pinfunction "DOUT_2") (pintype "passive"))
    )
    (net (code "40") (name "Net-(L*37-DIN)") (class "Default")
      (node (ref "L*37") (pin "4") (pinfunction "DIN_4") (pintype "passive"))
      (node (ref "L*38") (pin "2") (pinfunction "DOUT_2") (pintype "passive"))
    )
    (net (code "41") (name "Net-(L*38-DIN)") (class "Default")
      (node (ref "L*38") (pin "4") (pinfunction "DIN_4") (pintype "passive"))
      (node (ref "L*39") (pin "2") (pinfunction "DOUT_2") (pintype "passive"))
    )
    (net (code "42") (name "Net-(L*39-DIN)") (class "Default")
      (node (ref "L*39") (pin "4") (pinfunction "DIN_4") (pintype "passive"))
      (node (ref "L*40") (pin "2") (pinfunction "DOUT_2") (pintype "passive"))
    )
    (net (code "43") (name "Net-(L*40-DIN)") (class "Default")
      (node (ref "L*40") (pin "4") (pinfunction "DIN_4") (pintype "passive"))
      (node (ref "L*41") (pin "2") (pinfunction "DOUT_2") (pintype "passive"))
    )
    (net (code "44") (name "Net-(L*41-DIN)") (class "Default")
      (node (ref "L*41") (pin "4") (pinfunction "DIN_4") (pintype "passive"))
      (node (ref "L*42") (pin "2") (pinfunction "DOUT_2") (pintype "passive"))
    )
    (net (code "45") (name "Net-(L*42-DIN)") (class "Default")
      (node (ref "L*42") (pin "4") (pinfunction "DIN_4") (pintype "passive"))
      (node (ref "L*43") (pin "2") (pinfunction "DOUT_2") (pintype "passive"))
    )
    (net (code "46") (name "Net-(L*43-DIN)") (class "Default")
      (node (ref "L*43") (pin "4") (pinfunction "DIN_4") (pintype "passive"))
      (node (ref "L*44") (pin "2") (pinfunction "DOUT_2") (pintype "passive"))
    )
    (net (code "47") (name "Net-(L*44-DIN)") (class "Default")
      (node (ref "L*44") (pin "4") (pinfunction "DIN_4") (pintype "passive"))
      (node (ref "L*45") (pin "2") (pinfunction "DOUT_2") (pintype "passive"))
    )
    (net (code "48") (name "Net-(L*45-DIN)") (class "Default")
      (node (ref "L*45") (pin "4") (pinfunction "DIN_4") (pintype "passive"))
      (node (ref "L*46") (pin "2") (pinfunction "DOUT_2") (pintype "passive"))
    )
    (net (code "49") (name "Net-(L*46-DIN)") (class "Default")
      (node (ref "L*46") (pin "4") (pinfunction "DIN_4") (pintype "passive"))
      (node (ref "L*47") (pin "2") (pinfunction "DOUT_2") (pintype "passive"))
    )
    (net (code "50") (name "Net-(L*47-DIN)") (class "Default")
      (node (ref "L*47") (pin "4") (pinfunction "DIN_4") (pintype "passive"))
      (node (ref "L*48") (pin "2") (pinfunction "DOUT_2") (pintype "passive"))
    )
    (net (code "51") (name "Net-(L*48-DIN)") (class "Default")
      (node (ref "L*48") (pin "4") (pinfunction "DIN_4") (pintype "passive"))
      (node (ref "L*49") (pin "2") (pinfunction "DOUT_2") (pintype "passive"))
    )
    (net (code "52") (name "Net-(L*49-DIN)") (class "Default")
      (node (ref "L*49") (pin "4") (pinfunction "DIN_4") (pintype "passive"))
      (node (ref "L*50") (pin "2") (pinfunction "DOUT_2") (pintype "passive"))
    )
    (net (code "53") (name "Net-(L*50-DIN)") (class "Default")
      (node (ref "L*50") (pin "4") (pinfunction "DIN_4") (pintype "passive"))
      (node (ref "L*51") (pin "2") (pinfunction "DOUT_2") (pintype "passive"))
    )
    (net (code "54") (name "Net-(L*51-DIN)") (class "Default")
      (node (ref "L*51") (pin "4") (pinfunction "DIN_4") (pintype "passive"))
      (node (ref "L*52") (pin "2") (pinfunction "DOUT_2") (pintype "passive"))
    )
    (net (code "55") (name "Net-(L*52-DIN)") (class "Default")
      (node (ref "L*52") (pin "4") (pinfunction "DIN_4") (pintype "passive"))
      (node (ref "L*53") (pin "2") (pinfunction "DOUT_2") (pintype "passive"))
    )
    (net (code "56") (name "Net-(L*53-DIN)") (class "Default")
      (node (ref "L*53") (pin "4") (pinfunction "DIN_4") (pintype "passive"))
      (node (ref "L*54") (pin "2") (pinfunction "DOUT_2") (pintype "passive"))
    )
    (net (code "57") (name "Net-(L*54-DIN)") (class "Default")
      (node (ref "L*54") (pin "4") (pinfunction "DIN_4") (pintype "passive"))
      (node (ref "L*55") (pin "2") (pinfunction "DOUT_2") (pintype "passive"))
    )
    (net (code "58") (name "Net-(L*55-DIN)") (class "Default")
      (node (ref "L*55") (pin "4") (pinfunction "DIN_4") (pintype "passive"))
      (node (ref "L*56") (pin "2") (pinfunction "DOUT_2") (pintype "passive"))
    )
    (net (code "59") (name "Net-(L*56-DIN)") (class "Default")
      (node (ref "L*56") (pin "4") (pinfunction "DIN_4") (pintype "passive"))
      (node (ref "L*57") (pin "2") (pinfunction "DOUT_2") (pintype "passive"))
    )
    (net (code "60") (name "Net-(L*57-DIN)") (class "Default")
      (node (ref "L*57") (pin "4") (pinfunction "DIN_4") (pintype "passive"))
      (node (ref "L*58") (pin "2") (pinfunction "DOUT_2") (pintype "passive"))
    )
    (net (code "61") (name "Net-(L*58-DIN)") (class "Default")
      (node (ref "L*58") (pin "4") (pinfunction "DIN_4") (pintype "passive"))
      (node (ref "L*59") (pin "2") (pinfunction "DOUT_2") (pintype "passive"))
    )
    (net (code "62") (name "Net-(L*59-DIN)") (class "Default")
      (node (ref "L*59") (pin "4") (pinfunction "DIN_4") (pintype "passive"))
      (node (ref "L*60") (pin "2") (pinfunction "DOUT_2") (pintype "passive"))
    )
    (net (code "63") (name "Net-(L*60-DIN)") (class "Default")
      (node (ref "L*60") (pin "4") (pinfunction "DIN_4") (pintype "passive"))
      (node (ref "L*61") (pin "2") (pinfunction "DOUT_2") (pintype "passive"))
    )
    (net (code "64") (name "Net-(L*61-DIN)") (class "Default")
      (node (ref "L*61") (pin "4") (pinfunction "DIN_4") (pintype "passive"))
      (node (ref "L*62") (pin "2") (pinfunction "DOUT_2") (pintype "passive"))
    )
    (net (code "65") (name "Net-(L*62-DIN)") (class "Default")
      (node (ref "L*62") (pin "4") (pinfunction "DIN_4") (pintype "passive"))
      (node (ref "L*63") (pin "2") (pinfunction "DOUT_2") (pintype "passive"))
    )
    (net (code "66") (name "Net-(L*63-DIN)") (class "Default")
      (node (ref "L*63") (pin "4") (pinfunction "DIN_4") (pintype "passive"))
      (node (ref "L*64") (pin "2") (pinfunction "DOUT_2") (pintype "passive"))
    )
    (net (code "67") (name "Net-(L*64-DIN)") (class "Default")
      (node (ref "L*64") (pin "4") (pinfunction "DIN_4") (pintype "passive"))
      (node (ref "L*65") (pin "2") (pinfunction "DOUT_2") (pintype "passive"))
    )
    (net (code "68") (name "Net-(L*65-DIN)") (class "Default")
      (node (ref "L*65") (pin "4") (pinfunction "DIN_4") (pintype "passive"))
      (node (ref "L*66") (pin "2") (pinfunction "DOUT_2") (pintype "passive"))
    )
    (net (code "69") (name "Net-(L*66-DIN)") (class "Default")
      (node (ref "L*66") (pin "4") (pinfunction "DIN_4") (pintype "passive"))
      (node (ref "L*67") (pin "2") (pinfunction "DOUT_2") (pintype "passive"))
    )
    (net (code "70") (name "Net-(L*67-DIN)") (class "Default")
      (node (ref "L*67") (pin "4") (pinfunction "DIN_4") (pintype "passive"))
      (node (ref "L*68") (pin "2") (pinfunction "DOUT_2") (pintype "passive"))
    )
    (net (code "71") (name "Net-(L*68-DIN)") (class "Default")
      (node (ref "L*68") (pin "4") (pinfunction "DIN_4") (pintype "passive"))
      (node (ref "L*69") (pin "2") (pinfunction "DOUT_2") (pintype "passive"))
    )
    (net (code "72") (name "Net-(L*69-DIN)") (class "Default")
      (node (ref "L*69") (pin "4") (pinfunction "DIN_4") (pintype "passive"))
      (node (ref "L*70") (pin "2") (pinfunction "DOUT_2") (pintype "passive"))
    )
    (net (code "73") (name "Net-(L*70-DIN)") (class "Default")
      (node (ref "L*70") (pin "4") (pinfunction "DIN_4") (pintype "passive"))
      (node (ref "L*71") (pin "2") (pinfunction "DOUT_2") (pintype "passive"))
    )
    (net (code "74") (name "Net-(L*71-DIN)") (class "Default")
      (node (ref "L*71") (pin "4") (pinfunction "DIN_4") (pintype "passive"))
      (node (ref "L*72") (pin "2") (pinfunction "DOUT_2") (pintype "passive"))
    )
    (net (code "75") (name "Net-(L*72-DIN)") (class "Default")
      (node (ref "L*72") (pin "4") (pinfunction "DIN_4") (pintype "passive"))
      (node (ref "L*73") (pin "2") (pinfunction "DOUT_2") (pintype "passive"))
    )
    (net (code "76") (name "Net-(L*73-DIN)") (class "Default")
      (node (ref "L*73") (pin "4") (pinfunction "DIN_4") (pintype "passive"))
      (node (ref "L*74") (pin "2") (pinfunction "DOUT_2") (pintype "passive"))
    )
    (net (code "77") (name "Net-(L*74-DIN)") (class "Default")
      (node (ref "L*74") (pin "4") (pinfunction "DIN_4") (pintype "passive"))
      (node (ref "L*75") (pin "2") (pinfunction "DOUT_2") (pintype "passive"))
    )
    (net (code "78") (name "Net-(L*75-DIN)") (class "Default")
      (node (ref "L*75") (pin "4") (pinfunction "DIN_4") (pintype "passive"))
      (node (ref "L*76") (pin "2") (pinfunction "DOUT_2") (pintype "passive"))
    )
    (net (code "79") (name "Net-(L*76-DIN)") (class "Default")
      (node (ref "L*76") (pin "4") (pinfunction "DIN_4") (pintype "passive"))
      (node (ref "L*77") (pin "2") (pinfunction "DOUT_2") (pintype "passive"))
    )
    (net (code "80") (name "Net-(L*77-DIN)") (class "Default")
      (node (ref "L*77") (pin "4") (pinfunction "DIN_4") (pintype "passive"))
      (node (ref "L*78") (pin "2") (pinfunction "DOUT_2") (pintype "passive"))
    )
    (net (code "81") (name "Net-(L*78-DIN)") (class "Default")
      (node (ref "L*78") (pin "4") (pinfunction "DIN_4") (pintype "passive"))
      (node (ref "L*79") (pin "2") (pinfunction "DOUT_2") (pintype "passive"))
    )
    (net (code "82") (name "Net-(L*79-DIN)") (class "Default")
      (node (ref "L*79") (pin "4") (pinfunction "DIN_4") (pintype "passive"))
      (node (ref "L*80") (pin "2") (pinfunction "DOUT_2") (pintype "passive"))
    )
    (net (code "83") (name "Net-(L*80-DIN)") (class "Default")
      (node (ref "L*80") (pin "4") (pinfunction "DIN_4") (pintype "passive"))
      (node (ref "L*81") (pin "2") (pinfunction "DOUT_2") (pintype "passive"))
    )
    (net (code "84") (name "Net-(L*81-DIN)") (class "Default")
      (node (ref "L*81") (pin "4") (pinfunction "DIN_4") (pintype "passive"))
      (node (ref "L*82") (pin "2") (pinfunction "DOUT_2") (pintype "passive"))
    )
    (net (code "85") (name "Net-(L*82-DIN)") (class "Default")
      (node (ref "L*82") (pin "4") (pinfunction "DIN_4") (pintype "passive"))
      (node (ref "L*83") (pin "2") (pinfunction "DOUT_2") (pintype "passive"))
    )
    (net (code "86") (name "Net-(L*83-DIN)") (class "Default")
      (node (ref "L*83") (pin "4") (pinfunction "DIN_4") (pintype "passive"))
      (node (ref "L*84") (pin "2") (pinfunction "DOUT_2") (pintype "passive"))
    )
    (net (code "87") (name "unconnected-(L*1-DOUT-Pad2)") (class "Default")
      (node (ref "L*1") (pin "2") (pinfunction "DOUT_2") (pintype "passive"))
    )
  )
)
